# base.net
KiCad netlist of a schematic drawn in EAGLE
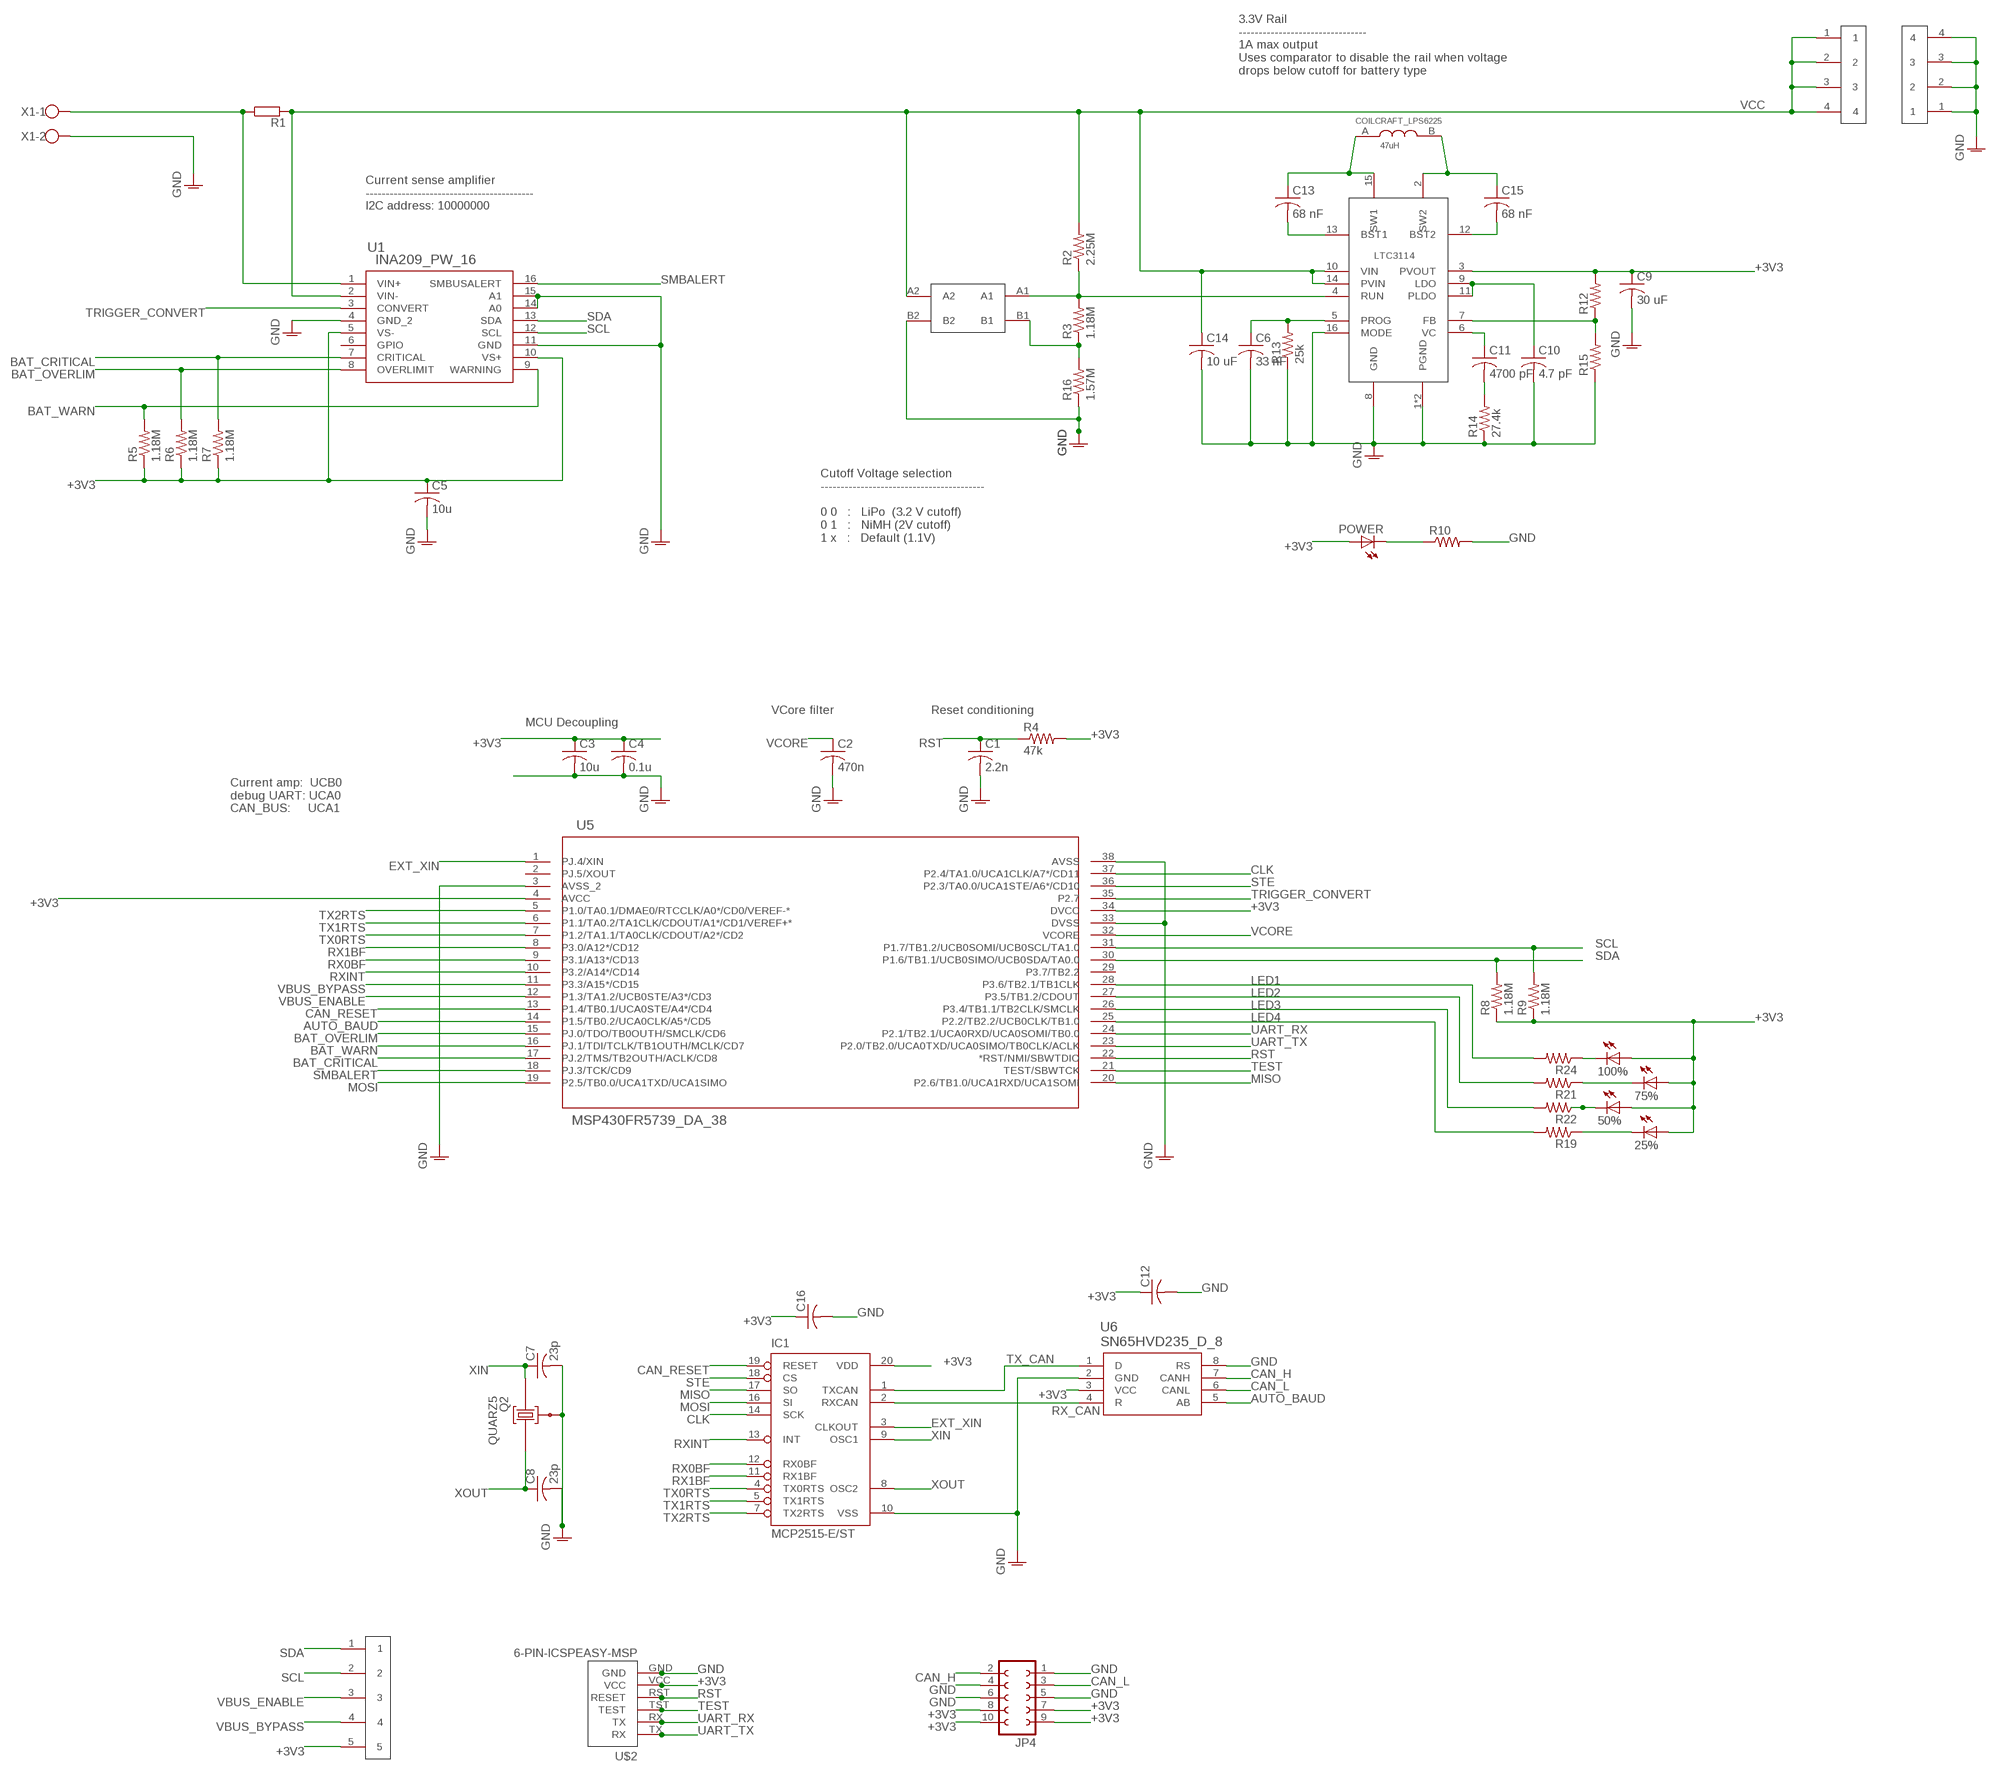
[diagram p0: schematic, sheet 1]

(export (version "E")
  (design (tool "Eeschema 10.0.6"))
  (components
    (comp (ref "25%")
      (value "LEDCHIP-LED0603")
      (footprint "eagle-import:CHIP-LED0603")
      (libsource (lib "eagle-import") (part "LEDCHIP-LED0603"))
    )
    (comp (ref "50%")
      (value "LEDCHIP-LED0603")
      (footprint "eagle-import:CHIP-LED0603")
      (libsource (lib "eagle-import") (part "LEDCHIP-LED0603"))
    )
    (comp (ref "75%")
      (value "LEDCHIP-LED0603")
      (footprint "eagle-import:CHIP-LED0603")
      (libsource (lib "eagle-import") (part "LEDCHIP-LED0603"))
    )
    (comp (ref "100%")
      (value "LEDCHIP-LED0603")
      (footprint "eagle-import:CHIP-LED0603")
      (libsource (lib "eagle-import") (part "LEDCHIP-LED0603"))
    )
    (comp (ref "C1")
      (value "2.2n")
      (footprint "eagle-import:C1206")
      (libsource (lib "eagle-import") (part "C-USC1206"))
    )
    (comp (ref "C2")
      (value "470n")
      (footprint "eagle-import:C1206")
      (libsource (lib "eagle-import") (part "C-USC1206"))
    )
    (comp (ref "C3")
      (value "10u")
      (footprint "eagle-import:C1206")
      (libsource (lib "eagle-import") (part "C-USC1206"))
    )
    (comp (ref "C4")
      (value "0.1u")
      (footprint "eagle-import:C1206")
      (libsource (lib "eagle-import") (part "C-USC1206"))
    )
    (comp (ref "C5")
      (value "10u")
      (footprint "eagle-import:C1206")
      (libsource (lib "eagle-import") (part "C-USC1206"))
    )
    (comp (ref "C6")
      (value "33 nF")
      (footprint "eagle-import:C0805")
      (libsource (lib "eagle-import") (part "C-USC0805"))
    )
    (comp (ref "C7")
      (value "23p")
      (footprint "eagle-import:C1206")
      (libsource (lib "eagle-import") (part "C-USC1206"))
    )
    (comp (ref "C8")
      (value "23p")
      (footprint "eagle-import:C1206")
      (libsource (lib "eagle-import") (part "C-USC1206"))
    )
    (comp (ref "C9")
      (value "30 uF")
      (footprint "eagle-import:C0805")
      (libsource (lib "eagle-import") (part "C-USC0805"))
    )
    (comp (ref "C10")
      (value "4.7 pF")
      (footprint "eagle-import:C0805")
      (libsource (lib "eagle-import") (part "C-USC0805"))
    )
    (comp (ref "C11")
      (value "4700 pF")
      (footprint "eagle-import:C0805")
      (libsource (lib "eagle-import") (part "C-USC0805"))
    )
    (comp (ref "C12")
      (value "C-USC0603")
      (footprint "eagle-import:C0603")
      (libsource (lib "eagle-import") (part "C-USC0603"))
    )
    (comp (ref "C13")
      (value "68 nF")
      (footprint "eagle-import:C0805")
      (libsource (lib "eagle-import") (part "C-USC0805"))
    )
    (comp (ref "C14")
      (value "10 uF")
      (footprint "eagle-import:C0805")
      (libsource (lib "eagle-import") (part "C-USC0805"))
    )
    (comp (ref "C15")
      (value "68 nF")
      (footprint "eagle-import:C0805")
      (libsource (lib "eagle-import") (part "C-USC0805"))
    )
    (comp (ref "C16")
      (value "C-USC0603")
      (footprint "eagle-import:C0603")
      (libsource (lib "eagle-import") (part "C-USC0603"))
    )
    (comp (ref "COILCRAFT_LPS6225")
      (value "47uH")
      (footprint "eagle-import:INDUCTOR")
      (libsource (lib "eagle-import") (part "COILCRAFT_LPS6225"))
    )
    (comp (ref "IC1")
      (value "MCP2515-E/ST")
      (footprint "eagle-import:TSSOP20")
      (libsource (lib "eagle-import") (part "MCP2515-E/ST"))
    )
    (comp (ref "JP4")
      (value "FE05-2")
      (footprint "eagle-import:FE05-2")
      (libsource (lib "eagle-import") (part "FE05-2"))
    )
    (comp (ref "POWER")
      (value "LEDCHIP-LED0603")
      (footprint "eagle-import:CHIP-LED0603")
      (libsource (lib "eagle-import") (part "LEDCHIP-LED0603"))
    )
    (comp (ref "Q2")
      (value "QUARZ5")
      (footprint "eagle-import:QUARZ5")
      (libsource (lib "eagle-import") (part "QUARZ5"))
    )
    (comp (ref "R1")
      (value "SMR")
      (footprint "eagle-import:SMR")
      (libsource (lib "eagle-import") (part "SMR"))
    )
    (comp (ref "R2")
      (value "2.25M")
      (footprint "eagle-import:R0805")
      (libsource (lib "eagle-import") (part "R-US_R0805"))
    )
    (comp (ref "R3")
      (value "1.18M")
      (footprint "eagle-import:R0805")
      (libsource (lib "eagle-import") (part "R-US_R0805"))
    )
    (comp (ref "R4")
      (value "47k")
      (footprint "eagle-import:R1206")
      (libsource (lib "eagle-import") (part "R-US_R1206"))
    )
    (comp (ref "R5")
      (value "1.18M")
      (footprint "eagle-import:R0805")
      (libsource (lib "eagle-import") (part "R-US_R0805"))
    )
    (comp (ref "R6")
      (value "1.18M")
      (footprint "eagle-import:R0805")
      (libsource (lib "eagle-import") (part "R-US_R0805"))
    )
    (comp (ref "R7")
      (value "1.18M")
      (footprint "eagle-import:R0805")
      (libsource (lib "eagle-import") (part "R-US_R0805"))
    )
    (comp (ref "R8")
      (value "1.18M")
      (footprint "eagle-import:R0805")
      (libsource (lib "eagle-import") (part "R-US_R0805"))
    )
    (comp (ref "R9")
      (value "1.18M")
      (footprint "eagle-import:R0805")
      (libsource (lib "eagle-import") (part "R-US_R0805"))
    )
    (comp (ref "R10")
      (value "R-US_R0603")
      (footprint "eagle-import:R0603")
      (libsource (lib "eagle-import") (part "R-US_R0603"))
    )
    (comp (ref "R12")
      (value "R-US_M0805")
      (footprint "eagle-import:M0805")
      (libsource (lib "eagle-import") (part "R-US_M0805"))
    )
    (comp (ref "R13")
      (value "25k")
      (footprint "eagle-import:M0805")
      (libsource (lib "eagle-import") (part "R-US_M0805"))
    )
    (comp (ref "R14")
      (value "27.4k")
      (footprint "eagle-import:M0805")
      (libsource (lib "eagle-import") (part "R-US_M0805"))
    )
    (comp (ref "R15")
      (value "R-US_M0805")
      (footprint "eagle-import:M0805")
      (libsource (lib "eagle-import") (part "R-US_M0805"))
    )
    (comp (ref "R16")
      (value "1.57M")
      (footprint "eagle-import:R0805")
      (libsource (lib "eagle-import") (part "R-US_R0805"))
    )
    (comp (ref "R19")
      (value "R-US_R0603")
      (footprint "eagle-import:R0603")
      (libsource (lib "eagle-import") (part "R-US_R0603"))
    )
    (comp (ref "R21")
      (value "R-US_R0603")
      (footprint "eagle-import:R0603")
      (libsource (lib "eagle-import") (part "R-US_R0603"))
    )
    (comp (ref "R22")
      (value "R-US_R0603")
      (footprint "eagle-import:R0603")
      (libsource (lib "eagle-import") (part "R-US_R0603"))
    )
    (comp (ref "R24")
      (value "R-US_R0603")
      (footprint "eagle-import:R0603")
      (libsource (lib "eagle-import") (part "R-US_R0603"))
    )
    (comp (ref "U$1")
      (value "LTC3114")
      (footprint "eagle-import:TSSOP-16")
      (libsource (lib "eagle-import") (part "LTC3114"))
    )
    (comp (ref "U$2")
      (value "6-PIN-ICSPEASY-MSP")
      (footprint "eagle-import:EASYMSP-6PIN")
      (libsource (lib "eagle-import") (part "6-PIN-ICSPEASY-MSP"))
    )
    (comp (ref "U$3")
      (value "1X4_HEADER")
      (footprint "eagle-import:1X4-.1HEADER")
      (libsource (lib "eagle-import") (part "1X4_HEADER"))
    )
    (comp (ref "U$4")
      (value "1X5_HEADER")
      (footprint "eagle-import:1X5-.1HEADER")
      (libsource (lib "eagle-import") (part "1X5_HEADER"))
    )
    (comp (ref "U$5")
      (value "76SB02T")
      (footprint "eagle-import:DIP-4")
      (libsource (lib "eagle-import") (part "76SB02T"))
    )
    (comp (ref "U$11")
      (value "1X4_HEADER")
      (footprint "eagle-import:1X4-.1HEADER")
      (libsource (lib "eagle-import") (part "1X4_HEADER"))
    )
    (comp (ref "U1")
      (value "INA209_PW_16")
      (footprint "eagle-import:PW16")
      (fields
        (field (name "GENERIC_PART_NUMBER") "INA209")
        (field (name "MANUFACTURER") "Texas Instruments")
        (field (name "MANUFACTURER_PART_NUMBER") "ina209_pw_16")
      )
      (libsource (lib "eagle-import") (part "INA209_PW_16"))
    )
    (comp (ref "U5")
      (value "MSP430FR5739_DA_38")
      (footprint "eagle-import:DA38")
      (fields
        (field (name "GENERIC_PART_NUMBER") "MSP430FR5739")
        (field (name "MANUFACTURER") "Texas Instruments")
        (field (name "MANUFACTURER_PART_NUMBER") "msp430fr5739_da_38")
      )
      (libsource (lib "eagle-import") (part "MSP430FR5739_DA_38"))
    )
    (comp (ref "U6")
      (value "SN65HVD235_D_8")
      (footprint "eagle-import:D8")
      (fields
        (field (name "GENERIC_PART_NUMBER") "SN65HVD235")
        (field (name "MANUFACTURER") "Texas Instruments")
        (field (name "MANUFACTURER_PART_NUMBER") "sn65hvd235_d_8")
      )
      (libsource (lib "eagle-import") (part "SN65HVD235_D_8"))
    )
    (comp (ref "X1")
      (value "W237-102")
      (footprint "eagle-import:W237-102")
      (fields (field (name "MPN") "237-102"))
      (libsource (lib "eagle-import") (part "W237-102"))
    )
  )
  (nets
    (net (code "1") (name "/+3V3") (class "Default")
      (node (ref "100%") (pin "A") (pinfunction "A_A") (pintype "passive"))
      (node (ref "25%") (pin "A") (pinfunction "A_A") (pintype "passive"))
      (node (ref "50%") (pin "A") (pinfunction "A_A") (pintype "passive"))
      (node (ref "75%") (pin "A") (pinfunction "A_A") (pintype "passive"))
      (node (ref "C12") (pin "1") (pinfunction "1_1") (pintype "passive"))
      (node (ref "C16") (pin "1") (pinfunction "1_1") (pintype "passive"))
      (node (ref "C3") (pin "1") (pinfunction "1_1") (pintype "passive"))
      (node (ref "C4") (pin "1") (pinfunction "1_1") (pintype "passive"))
      (node (ref "C5") (pin "1") (pinfunction "1_1") (pintype "passive"))
      (node (ref "C9") (pin "1") (pinfunction "1_1") (pintype "passive"))
      (node (ref "IC1") (pin "20") (pinfunction "VDD_20") (pintype "power_in"))
      (node (ref "JP4") (pin "10") (pinfunction "10_10") (pintype "passive"))
      (node (ref "JP4") (pin "7") (pinfunction "7_7") (pintype "passive"))
      (node (ref "JP4") (pin "8") (pinfunction "8_8") (pintype "passive"))
      (node (ref "JP4") (pin "9") (pinfunction "9_9") (pintype "passive"))
      (node (ref "POWER") (pin "A") (pinfunction "A_A") (pintype "passive"))
      (node (ref "R12") (pin "2") (pinfunction "2_2") (pintype "passive"))
      (node (ref "R4") (pin "2") (pinfunction "2_2") (pintype "passive"))
      (node (ref "R5") (pin "1") (pinfunction "1_1") (pintype "passive"))
      (node (ref "R6") (pin "1") (pinfunction "1_1") (pintype "passive"))
      (node (ref "R7") (pin "1") (pinfunction "1_1") (pintype "passive"))
      (node (ref "R8") (pin "1") (pinfunction "1_1") (pintype "passive"))
      (node (ref "R9") (pin "1") (pinfunction "1_1") (pintype "passive"))
      (node (ref "U$1") (pin "3") (pinfunction "PVOUT_3") (pintype "bidirectional"))
      (node (ref "U$2") (pin "VCC") (pinfunction "VCC_VCC") (pintype "bidirectional"))
      (node (ref "U$4") (pin "5") (pinfunction "5_5") (pintype "bidirectional"))
      (node (ref "U1") (pin "10") (pinfunction "VS+_10") (pintype "power_in"))
      (node (ref "U1") (pin "5") (pinfunction "VS-_5") (pintype "power_in"))
      (node (ref "U5") (pin "34") (pinfunction "DVCC_34") (pintype "power_in"))
      (node (ref "U5") (pin "4") (pinfunction "AVCC_4") (pintype "power_in"))
      (node (ref "U6") (pin "3") (pinfunction "VCC_3") (pintype "power_in"))
    )
    (net (code "2") (name "/AUTO_BAUD") (class "Default")
      (node (ref "U5") (pin "14") (pinfunction "P1.5/TB0.2/UCA0CLK/A5*/CD5_14") (pintype "bidirectional"))
      (node (ref "U6") (pin "5") (pinfunction "AB_5") (pintype "input"))
    )
    (net (code "3") (name "/BAT_CRITICAL") (class "Default")
      (node (ref "R7") (pin "2") (pinfunction "2_2") (pintype "passive"))
      (node (ref "U1") (pin "7") (pinfunction "CRITICAL_7") (pintype "output"))
      (node (ref "U5") (pin "17") (pinfunction "PJ.2/TMS/TB2OUTH/ACLK/CD8_17") (pintype "bidirectional"))
    )
    (net (code "4") (name "/BAT_OVERLIM") (class "Default")
      (node (ref "R6") (pin "2") (pinfunction "2_2") (pintype "passive"))
      (node (ref "U1") (pin "8") (pinfunction "OVERLIMIT_8") (pintype "output"))
      (node (ref "U5") (pin "15") (pinfunction "PJ.0/TDO/TB0OUTH/SMCLK/CD6_15") (pintype "bidirectional"))
    )
    (net (code "5") (name "/BAT_WARN") (class "Default")
      (node (ref "R5") (pin "2") (pinfunction "2_2") (pintype "passive"))
      (node (ref "U1") (pin "9") (pinfunction "WARNING_9") (pintype "output"))
      (node (ref "U5") (pin "16") (pinfunction "PJ.1/TDI/TCLK/TB1OUTH/MCLK/CD7_16") (pintype "bidirectional"))
    )
    (net (code "6") (name "/CAN_H") (class "Default")
      (node (ref "JP4") (pin "2") (pinfunction "2_2") (pintype "passive"))
      (node (ref "U6") (pin "7") (pinfunction "CANH_7") (pintype "output"))
    )
    (net (code "7") (name "/CAN_L") (class "Default")
      (node (ref "JP4") (pin "3") (pinfunction "3_3") (pintype "passive"))
      (node (ref "U6") (pin "6") (pinfunction "CANL_6") (pintype "output"))
    )
    (net (code "8") (name "/CAN_RESET") (class "Default")
      (node (ref "IC1") (pin "19") (pinfunction "RESET_19") (pintype "input"))
      (node (ref "U5") (pin "13") (pinfunction "P1.4/TB0.1/UCA0STE/A4*/CD4_13") (pintype "bidirectional"))
    )
    (net (code "9") (name "/CLK") (class "Default")
      (node (ref "IC1") (pin "14") (pinfunction "SCK_14") (pintype "input"))
      (node (ref "U5") (pin "37") (pinfunction "P2.4/TA1.0/UCA1CLK/A7*/CD11_37") (pintype "bidirectional"))
    )
    (net (code "10") (name "/EXT_XIN") (class "Default")
      (node (ref "IC1") (pin "3") (pinfunction "CLKOUT_3") (pintype "output"))
      (node (ref "U5") (pin "1") (pinfunction "PJ.4/XIN_1") (pintype "bidirectional"))
    )
    (net (code "11") (name "/LED1") (class "Default")
      (node (ref "R24") (pin "2") (pinfunction "2_2") (pintype "passive"))
      (node (ref "U5") (pin "28") (pinfunction "P3.6/TB2.1/TB1CLK_28") (pintype "bidirectional"))
    )
    (net (code "12") (name "/LED2") (class "Default")
      (node (ref "R21") (pin "2") (pinfunction "2_2") (pintype "passive"))
      (node (ref "U5") (pin "27") (pinfunction "P3.5/TB1.2/CDOUT_27") (pintype "bidirectional"))
    )
    (net (code "13") (name "/LED3") (class "Default")
      (node (ref "R22") (pin "2") (pinfunction "2_2") (pintype "passive"))
      (node (ref "U5") (pin "26") (pinfunction "P3.4/TB1.1/TB2CLK/SMCLK_26") (pintype "bidirectional"))
    )
    (net (code "14") (name "/LED4") (class "Default")
      (node (ref "R19") (pin "2") (pinfunction "2_2") (pintype "passive"))
      (node (ref "U5") (pin "25") (pinfunction "P2.2/TB2.2/UCB0CLK/TB1.0_25") (pintype "bidirectional"))
    )
    (net (code "15") (name "/MISO") (class "Default")
      (node (ref "IC1") (pin "17") (pinfunction "SO_17") (pintype "output"))
      (node (ref "U5") (pin "20") (pinfunction "P2.6/TB1.0/UCA1RXD/UCA1SOMI_20") (pintype "bidirectional"))
    )
    (net (code "16") (name "/MOSI") (class "Default")
      (node (ref "IC1") (pin "16") (pinfunction "SI_16") (pintype "input"))
      (node (ref "U5") (pin "19") (pinfunction "P2.5/TB0.0/UCA1TXD/UCA1SIMO_19") (pintype "bidirectional"))
    )
    (net (code "17") (name "/RST") (class "Default")
      (node (ref "C1") (pin "1") (pinfunction "1_1") (pintype "passive"))
      (node (ref "R4") (pin "1") (pinfunction "1_1") (pintype "passive"))
      (node (ref "U$2") (pin "RST") (pinfunction "RESET_RST") (pintype "bidirectional"))
      (node (ref "U5") (pin "22") (pinfunction "*RST/NMI/SBWTDIO_22") (pintype "bidirectional"))
    )
    (net (code "18") (name "/RX0BF") (class "Default")
      (node (ref "IC1") (pin "12") (pinfunction "RX0BF_12") (pintype "output"))
      (node (ref "U5") (pin "9") (pinfunction "P3.1/A13*/CD13_9") (pintype "bidirectional"))
    )
    (net (code "19") (name "/RX1BF") (class "Default")
      (node (ref "IC1") (pin "11") (pinfunction "RX1BF_11") (pintype "output"))
      (node (ref "U5") (pin "8") (pinfunction "P3.0/A12*/CD12_8") (pintype "bidirectional"))
    )
    (net (code "20") (name "/RXINT") (class "Default")
      (node (ref "IC1") (pin "13") (pinfunction "INT_13") (pintype "output"))
      (node (ref "U5") (pin "10") (pinfunction "P3.2/A14*/CD14_10") (pintype "bidirectional"))
    )
    (net (code "21") (name "/RX_CAN") (class "Default")
      (node (ref "IC1") (pin "2") (pinfunction "RXCAN_2") (pintype "input"))
      (node (ref "U6") (pin "4") (pinfunction "R_4") (pintype "input"))
    )
    (net (code "22") (name "/SCL") (class "Default")
      (node (ref "R9") (pin "2") (pinfunction "2_2") (pintype "passive"))
      (node (ref "U$4") (pin "2") (pinfunction "2_2") (pintype "bidirectional"))
      (node (ref "U1") (pin "12") (pinfunction "SCL_12") (pintype "passive"))
      (node (ref "U5") (pin "31") (pinfunction "P1.7/TB1.2/UCB0SOMI/UCB0SCL/TA1.0_31") (pintype "bidirectional"))
    )
    (net (code "23") (name "/SDA") (class "Default")
      (node (ref "R8") (pin "2") (pinfunction "2_2") (pintype "passive"))
      (node (ref "U$4") (pin "1") (pinfunction "1_1") (pintype "bidirectional"))
      (node (ref "U1") (pin "13") (pinfunction "SDA_13") (pintype "passive"))
      (node (ref "U5") (pin "30") (pinfunction "P1.6/TB1.1/UCB0SIMO/UCB0SDA/TA0.0_30") (pintype "bidirectional"))
    )
    (net (code "24") (name "/SMBALERT") (class "Default")
      (node (ref "U1") (pin "16") (pinfunction "SMBUSALERT_16") (pintype "output"))
      (node (ref "U5") (pin "18") (pinfunction "PJ.3/TCK/CD9_18") (pintype "bidirectional"))
    )
    (net (code "25") (name "/STE") (class "Default")
      (node (ref "IC1") (pin "18") (pinfunction "CS_18") (pintype "input"))
      (node (ref "U5") (pin "36") (pinfunction "P2.3/TA0.0/UCA1STE/A6*/CD10_36") (pintype "bidirectional"))
    )
    (net (code "26") (name "/TEST") (class "Default")
      (node (ref "U$2") (pin "TST") (pinfunction "TEST_TST") (pintype "bidirectional"))
      (node (ref "U5") (pin "21") (pinfunction "TEST/SBWTCK_21") (pintype "bidirectional"))
    )
    (net (code "27") (name "/TRIGGER_CONVERT") (class "Default")
      (node (ref "U1") (pin "3") (pinfunction "CONVERT_3") (pintype "passive"))
      (node (ref "U5") (pin "35") (pinfunction "P2.7_35") (pintype "bidirectional"))
    )
    (net (code "28") (name "/TX0RTS") (class "Default")
      (node (ref "IC1") (pin "4") (pinfunction "TX0RTS_4") (pintype "input"))
      (node (ref "U5") (pin "7") (pinfunction "P1.2/TA1.1/TA0CLK/CDOUT/A2*/CD2_7") (pintype "bidirectional"))
    )
    (net (code "29") (name "/TX1RTS") (class "Default")
      (node (ref "IC1") (pin "5") (pinfunction "TX1RTS_5") (pintype "input"))
      (node (ref "U5") (pin "6") (pinfunction "P1.1/TA0.2/TA1CLK/CDOUT/A1*/CD1/VEREF+*_6") (pintype "bidirectional"))
    )
    (net (code "30") (name "/TX2RTS") (class "Default")
      (node (ref "IC1") (pin "7") (pinfunction "TX2RTS_7") (pintype "input"))
      (node (ref "U5") (pin "5") (pinfunction "P1.0/TA0.1/DMAE0/RTCCLK/A0*/CD0/VEREF-*_5") (pintype "bidirectional"))
    )
    (net (code "31") (name "/TX_CAN") (class "Default")
      (node (ref "IC1") (pin "1") (pinfunction "TXCAN_1") (pintype "output"))
      (node (ref "U6") (pin "1") (pinfunction "D_1") (pintype "input"))
    )
    (net (code "32") (name "/UART_RX") (class "Default")
      (node (ref "U$2") (pin "RX") (pinfunction "TX_RX") (pintype "bidirectional"))
      (node (ref "U5") (pin "24") (pinfunction "P2.1/TB2.1/UCA0RXD/UCA0SOMI/TB0.0_24") (pintype "bidirectional"))
    )
    (net (code "33") (name "/UART_TX") (class "Default")
      (node (ref "U$2") (pin "TX") (pinfunction "RX_TX") (pintype "bidirectional"))
      (node (ref "U5") (pin "23") (pinfunction "P2.0/TB2.0/UCA0TXD/UCA0SIMO/TB0CLK/ACLK_23") (pintype "bidirectional"))
    )
    (net (code "34") (name "/VBUS_BYPASS") (class "Default")
      (node (ref "U$4") (pin "4") (pinfunction "4_4") (pintype "bidirectional"))
      (node (ref "U5") (pin "11") (pinfunction "P3.3/A15*/CD15_11") (pintype "bidirectional"))
    )
    (net (code "35") (name "/VBUS_ENABLE") (class "Default")
      (node (ref "U$4") (pin "3") (pinfunction "3_3") (pintype "bidirectional"))
      (node (ref "U5") (pin "12") (pinfunction "P1.3/TA1.2/UCB0STE/A3*/CD3_12") (pintype "bidirectional"))
    )
    (net (code "36") (name "/VCC") (class "Default")
      (node (ref "C14") (pin "1") (pinfunction "1_1") (pintype "passive"))
      (node (ref "R1") (pin "2") (pinfunction "2_2") (pintype "passive"))
      (node (ref "R2") (pin "2") (pinfunction "2_2") (pintype "passive"))
      (node (ref "U$1") (pin "10") (pinfunction "VIN_10") (pintype "bidirectional"))
      (node (ref "U$1") (pin "14") (pinfunction "PVIN_14") (pintype "bidirectional"))
      (node (ref "U$11") (pin "1") (pinfunction "1_1") (pintype "bidirectional"))
      (node (ref "U$11") (pin "2") (pinfunction "2_2") (pintype "bidirectional"))
      (node (ref "U$11") (pin "3") (pinfunction "3_3") (pintype "bidirectional"))
      (node (ref "U$11") (pin "4") (pinfunction "4_4") (pintype "bidirectional"))
      (node (ref "U$5") (pin "A2") (pinfunction "A2_A2") (pintype "bidirectional"))
      (node (ref "U1") (pin "2") (pinfunction "VIN-_2") (pintype "input"))
    )
    (net (code "37") (name "/VCORE") (class "Default")
      (node (ref "C2") (pin "1") (pinfunction "1_1") (pintype "passive"))
      (node (ref "U5") (pin "32") (pinfunction "VCORE_32") (pintype "power_in"))
    )
    (net (code "38") (name "/XIN") (class "Default")
      (node (ref "C7") (pin "1") (pinfunction "1_1") (pintype "passive"))
      (node (ref "IC1") (pin "9") (pinfunction "OSC1_9") (pintype "input"))
      (node (ref "Q2") (pin "2") (pinfunction "2_2") (pintype "passive"))
    )
    (net (code "39") (name "/XOUT") (class "Default")
      (node (ref "C8") (pin "1") (pinfunction "1_1") (pintype "passive"))
      (node (ref "IC1") (pin "8") (pinfunction "OSC2_8") (pintype "output"))
      (node (ref "Q2") (pin "1") (pinfunction "1_1") (pintype "passive"))
    )
    (net (code "40") (name "GND") (class "Default")
      (node (ref "C1") (pin "2") (pinfunction "2_2") (pintype "passive"))
      (node (ref "C10") (pin "2") (pinfunction "2_2") (pintype "passive"))
      (node (ref "C12") (pin "2") (pinfunction "2_2") (pintype "passive"))
      (node (ref "C14") (pin "2") (pinfunction "2_2") (pintype "passive"))
      (node (ref "C16") (pin "2") (pinfunction "2_2") (pintype "passive"))
      (node (ref "C2") (pin "2") (pinfunction "2_2") (pintype "passive"))
      (node (ref "C3") (pin "2") (pinfunction "2_2") (pintype "passive"))
      (node (ref "C4") (pin "2") (pinfunction "2_2") (pintype "passive"))
      (node (ref "C5") (pin "2") (pinfunction "2_2") (pintype "passive"))
      (node (ref "C6") (pin "2") (pinfunction "2_2") (pintype "passive"))
      (node (ref "C7") (pin "2") (pinfunction "2_2") (pintype "passive"))
      (node (ref "C8") (pin "2") (pinfunction "2_2") (pintype "passive"))
      (node (ref "C9") (pin "2") (pinfunction "2_2") (pintype "passive"))
      (node (ref "IC1") (pin "10") (pinfunction "VSS_10") (pintype "power_in"))
      (node (ref "JP4") (pin "1") (pinfunction "1_1") (pintype "passive"))
      (node (ref "JP4") (pin "4") (pinfunction "4_4") (pintype "passive"))
      (node (ref "JP4") (pin "5") (pinfunction "5_5") (pintype "passive"))
      (node (ref "JP4") (pin "6") (pinfunction "6_6") (pintype "passive"))
      (node (ref "Q2") (pin "GND@0") (pinfunction "0_GND@0") (pintype "passive"))
      (node (ref "R10") (pin "2") (pinfunction "2_2") (pintype "passive"))
      (node (ref "R13") (pin "1") (pinfunction "1_1") (pintype "passive"))
      (node (ref "R14") (pin "1") (pinfunction "1_1") (pintype "passive"))
      (node (ref "R15") (pin "1") (pinfunction "1_1") (pintype "passive"))
      (node (ref "R16") (pin "1") (pinfunction "1_1") (pintype "passive"))
      (node (ref "U$1") (pin "1") (pinfunction "PGND_1") (pintype "bidirectional"))
      (node (ref "U$1") (pin "16") (pinfunction "MODE_16") (pintype "bidirectional"))
      (node (ref "U$1") (pin "8") (pinfunction "GND_8") (pintype "bidirectional"))
      (node (ref "U$1") (pin "PAD") (pinfunction "PGND_PAD") (pintype "bidirectional"))
      (node (ref "U$2") (pin "GND") (pinfunction "GND_GND") (pintype "bidirectional"))
      (node (ref "U$3") (pin "1") (pinfunction "1_1") (pintype "bidirectional"))
      (node (ref "U$3") (pin "2") (pinfunction "2_2") (pintype "bidirectional"))
      (node (ref "U$3") (pin "3") (pinfunction "3_3") (pintype "bidirectional"))
      (node (ref "U$3") (pin "4") (pinfunction "4_4") (pintype "bidirectional"))
      (node (ref "U$5") (pin "B2") (pinfunction "B2_B2") (pintype "bidirectional"))
      (node (ref "U1") (pin "11") (pinfunction "GND_11") (pintype "power_in"))
      (node (ref "U1") (pin "14") (pinfunction "A0_14") (pintype "passive"))
      (node (ref "U1") (pin "15") (pinfunction "A1_15") (pintype "passive"))
      (node (ref "U1") (pin "4") (pinfunction "GND_2_4") (pintype "power_in"))
      (node (ref "U5") (pin "3") (pinfunction "AVSS_2_3") (pintype "power_in"))
      (node (ref "U5") (pin "33") (pinfunction "DVSS_33") (pintype "power_in"))
      (node (ref "U5") (pin "38") (pinfunction "AVSS_38") (pintype "power_in"))
      (node (ref "U6") (pin "2") (pinfunction "GND_2") (pintype "power_in"))
      (node (ref "U6") (pin "8") (pinfunction "RS_8") (pintype "input"))
      (node (ref "X1") (pin "2") (pinfunction "KL_2") (pintype "passive"))
    )
    (net (code "41") (name "Net-(25%-PadC)") (class "Default")
      (node (ref "25%") (pin "C") (pinfunction "C_C") (pintype "passive"))
      (node (ref "R19") (pin "1") (pinfunction "1_1") (pintype "passive"))
    )
    (net (code "42") (name "Net-(50%-PadC)") (class "Default")
      (node (ref "50%") (pin "C") (pinfunction "C_C") (pintype "passive"))
      (node (ref "R22") (pin "1") (pinfunction "1_1") (pintype "passive"))
    )
    (net (code "43") (name "Net-(75%-PadC)") (class "Default")
      (node (ref "75%") (pin "C") (pinfunction "C_C") (pintype "passive"))
      (node (ref "R21") (pin "1") (pinfunction "1_1") (pintype "passive"))
    )
    (net (code "44") (name "Net-(100%-PadC)") (class "Default")
      (node (ref "100%") (pin "C") (pinfunction "C_C") (pintype "passive"))
      (node (ref "R24") (pin "1") (pinfunction "1_1") (pintype "passive"))
    )
    (net (code "45") (name "Net-(C11-Pad2)") (class "Default")
      (node (ref "C11") (pin "2") (pinfunction "2_2") (pintype "passive"))
      (node (ref "R14") (pin "2") (pinfunction "2_2") (pintype "passive"))
    )
    (net (code "46") (name "Net-(POWER-PadC)") (class "Default")
      (node (ref "POWER") (pin "C") (pinfunction "C_C") (pintype "passive"))
      (node (ref "R10") (pin "1") (pinfunction "1_1") (pintype "passive"))
    )
    (net (code "47") (name "Net-(R16-Pad2)") (class "Default")
      (node (ref "R16") (pin "2") (pinfunction "2_2") (pintype "passive"))
      (node (ref "R3") (pin "1") (pinfunction "1_1") (pintype "passive"))
      (node (ref "U$5") (pin "B1") (pinfunction "B1_B1") (pintype "bidirectional"))
    )
    (net (code "48") (name "Net-(U$1-BST1)") (class "Default")
      (node (ref "C13") (pin "2") (pinfunction "2_2") (pintype "passive"))
      (node (ref "U$1") (pin "13") (pinfunction "BST1_13") (pintype "bidirectional"))
    )
    (net (code "49") (name "Net-(U$1-BST2)") (class "Default")
      (node (ref "C15") (pin "2") (pinfunction "2_2") (pintype "passive"))
      (node (ref "U$1") (pin "12") (pinfunction "BST2_12") (pintype "bidirectional"))
    )
    (net (code "50") (name "Net-(U$1-FB)") (class "Default")
      (node (ref "R12") (pin "1") (pinfunction "1_1") (pintype "passive"))
      (node (ref "R15") (pin "2") (pinfunction "2_2") (pintype "passive"))
      (node (ref "U$1") (pin "7") (pinfunction "FB_7") (pintype "bidirectional"))
    )
    (net (code "51") (name "Net-(U$1-LDO)") (class "Default")
      (node (ref "C10") (pin "1") (pinfunction "1_1") (pintype "passive"))
      (node (ref "U$1") (pin "11") (pinfunction "PLDO_11") (pintype "bidirectional"))
      (node (ref "U$1") (pin "9") (pinfunction "LDO_9") (pintype "bidirectional"))
    )
    (net (code "52") (name "Net-(U$1-PROG)") (class "Default")
      (node (ref "C6") (pin "1") (pinfunction "1_1") (pintype "passive"))
      (node (ref "R13") (pin "2") (pinfunction "2_2") (pintype "passive"))
      (node (ref "U$1") (pin "5") (pinfunction "PROG_5") (pintype "bidirectional"))
    )
    (net (code "53") (name "Net-(U$1-RUN)") (class "Default")
      (node (ref "R2") (pin "1") (pinfunction "1_1") (pintype "passive"))
      (node (ref "R3") (pin "2") (pinfunction "2_2") (pintype "passive"))
      (node (ref "U$1") (pin "4") (pinfunction "RUN_4") (pintype "bidirectional"))
      (node (ref "U$5") (pin "A1") (pinfunction "A1_A1") (pintype "bidirectional"))
    )
    (net (code "54") (name "Net-(U$1-SW1)") (class "Default")
      (node (ref "C13") (pin "1") (pinfunction "1_1") (pintype "passive"))
      (node (ref "COILCRAFT_LPS6225") (pin "A") (pinfunction "A_A") (pintype "bidirectional"))
      (node (ref "U$1") (pin "15") (pinfunction "SW1_15") (pintype "bidirectional"))
    )
    (net (code "55") (name "Net-(U$1-SW2)") (class "Default")
      (node (ref "C15") (pin "1") (pinfunction "1_1") (pintype "passive"))
      (node (ref "COILCRAFT_LPS6225") (pin "B") (pinfunction "B_B") (pintype "bidirectional"))
      (node (ref "U$1") (pin "2") (pinfunction "SW2_2") (pintype "bidirectional"))
    )
    (net (code "56") (name "Net-(U$1-VC)") (class "Default")
      (node (ref "C11") (pin "1") (pinfunction "1_1") (pintype "passive"))
      (node (ref "U$1") (pin "6") (pinfunction "VC_6") (pintype "bidirectional"))
    )
    (net (code "57") (name "Net-(U1-VIN+)") (class "Default")
      (node (ref "R1") (pin "1") (pinfunction "1_1") (pintype "passive"))
      (node (ref "U1") (pin "1") (pinfunction "VIN+_1") (pintype "input"))
      (node (ref "X1") (pin "1") (pinfunction "KL_1") (pintype "passive"))
    )
    (net (code "58") (name "unconnected-(U1-GPIO-Pad6)") (class "Default")
      (node (ref "U1") (pin "6") (pinfunction "GPIO_6") (pintype "passive"))
    )
    (net (code "59") (name "unconnected-(U5-P3.7{slash}TB2.2-Pad29)") (class "Default")
      (node (ref "U5") (pin "29") (pinfunction "P3.7/TB2.2_29") (pintype "bidirectional"))
    )
    (net (code "60") (name "unconnected-(U5-PJ.5{slash}XOUT-Pad2)") (class "Default")
      (node (ref "U5") (pin "2") (pinfunction "PJ.5/XOUT_2") (pintype "bidirectional"))
    )
  )
)
